# 1_P1_schdoc.net
KiCad netlist of a schematic drawn in Altium Designer
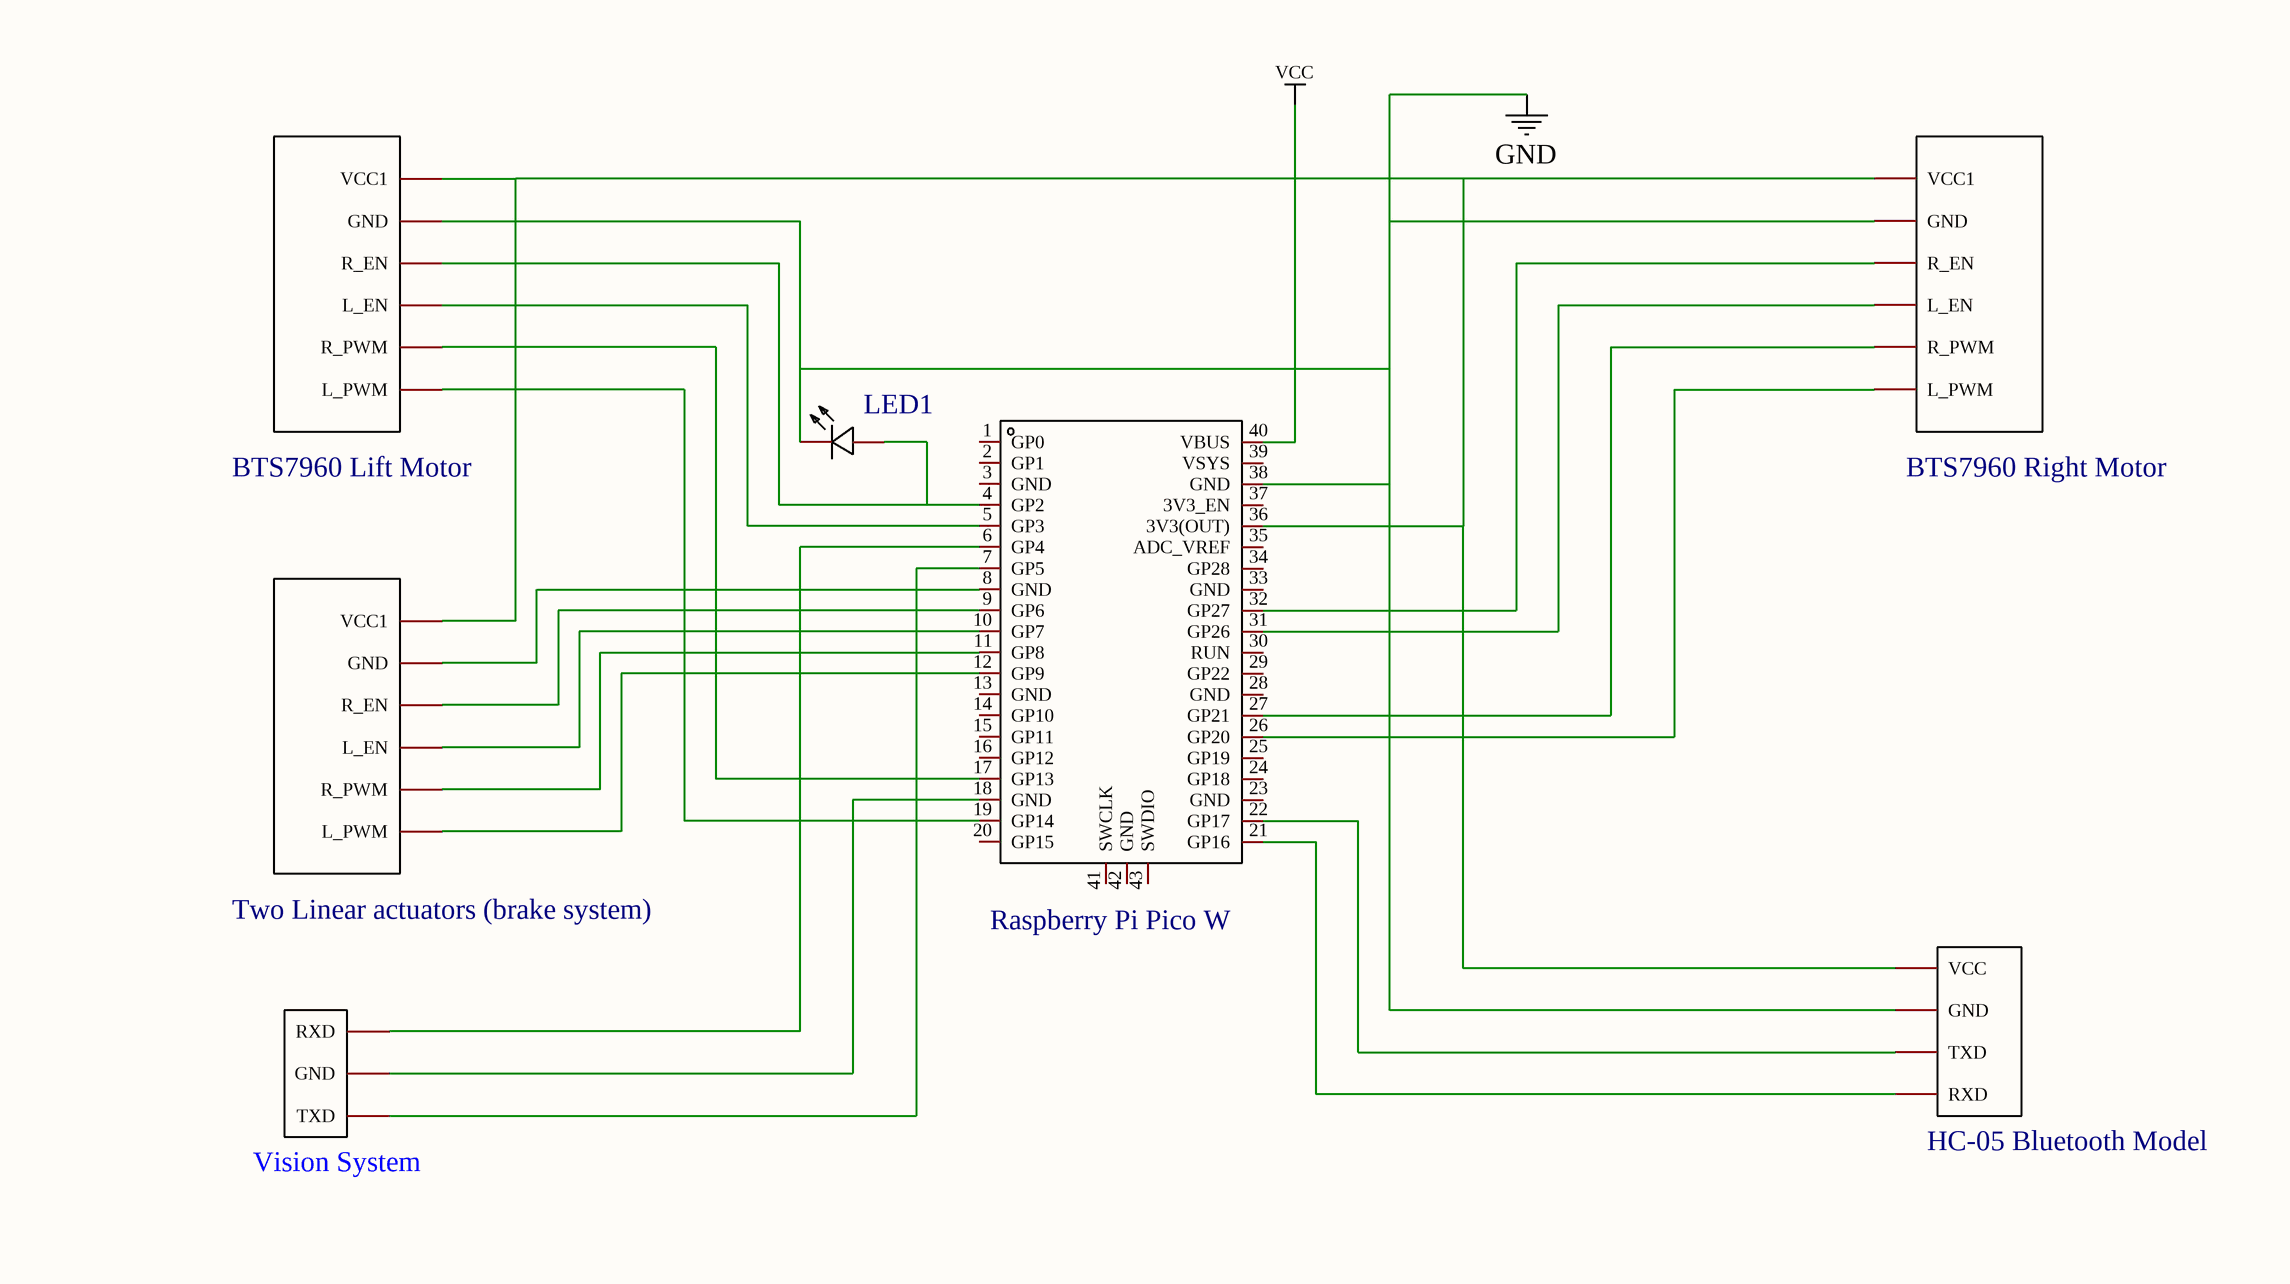
[diagram p0: 1_P1.schdoc.schdoc]

(export (version "E")
  (design (tool "Eeschema 10.0.6"))
  (components
    (comp (ref "LED1")
      (value "NCD0805R1")
      (fields (field (name "MANUFACTURER") "国星光电"))
      (libsource (lib "altium-import") (part "root_0_NCD0805R1_"))
    )
    (comp (ref "U1")
      (value "Raspberry Pi Pico W")
      (fields
        (field (name "NAME") "Raspberry Pi Pico W")
        (field (name "MANUFACTURER") "Raspberry Pi(树莓派)")
        (field (name "MANUFACTURER PART") "PICO")
      )
      (libsource (lib "altium-import") (part "root_0_PICO_"))
    )
    (comp (ref "U2")
      (value "HC-05 Bluetooth Model")
      (fields (field (name "NAME") "HC-05 Bluetooth Model"))
      (libsource (lib "altium-import") (part "root_0_mirrored_HC-05_"))
    )
    (comp (ref "U3")
      (value "BTS7960 Lift Motor")
      (fields (field (name "NAME") "BTS7960 Lift Motor"))
      (libsource (lib "altium-import") (part "root_0_Motor Driver_"))
    )
    (comp (ref "U4")
      (value "BTS7960 Right Motor")
      (fields (field (name "NAME") "BTS7960 Right Motor"))
      (libsource (lib "altium-import") (part "root_0_mirrored_Motor Driver_"))
    )
    (comp (ref "U5")
      (value "Vision System")
      (fields (field (name "DEVICE") "Vision System"))
      (libsource (lib "altium-import") (part "root_0_Vision System_"))
    )
    (comp (ref "U6")
      (value "Two Linear actuators (brake system)")
      (fields (field (name "NAME") "Two Linear actuators (brake system)"))
      (libsource (lib "altium-import") (part "root_0_Motor Driver_"))
    )
  )
  (nets
    (net (code "1") (name "GND") (class "Default")
      (node (ref "LED1") (pin "2") (pinfunction "-_2") (pintype "passive"))
      (node (ref "U1") (pin "38") (pinfunction "GND_38") (pintype "passive"))
      (node (ref "U2") (pin "2") (pinfunction "GND_2") (pintype "passive"))
      (node (ref "U3") (pin "2") (pinfunction "GND_2") (pintype "passive"))
      (node (ref "U4") (pin "2") (pinfunction "GND_2") (pintype "passive"))
    )
    (net (code "2") (name "Net-(LED1-+)") (class "Default")
      (node (ref "LED1") (pin "1") (pinfunction "+_1") (pintype "passive"))
      (node (ref "U1") (pin "4") (pinfunction "GP2_4") (pintype "passive"))
      (node (ref "U3") (pin "3") (pinfunction "R_EN_3") (pintype "passive"))
    )
    (net (code "3") (name "Net-(U1-3V3(OUT))") (class "Default")
      (node (ref "U1") (pin "36") (pinfunction "3V3(OUT)_36") (pintype "passive"))
      (node (ref "U2") (pin "1") (pinfunction "VCC_1") (pintype "passive"))
      (node (ref "U3") (pin "1") (pinfunction "VCC1_1") (pintype "passive"))
      (node (ref "U4") (pin "1") (pinfunction "VCC1_1") (pintype "passive"))
      (node (ref "U6") (pin "1") (pinfunction "VCC1_1") (pintype "passive"))
    )
    (net (code "4") (name "Net-(U1-GP3)") (class "Default")
      (node (ref "U1") (pin "5") (pinfunction "GP3_5") (pintype "passive"))
      (node (ref "U3") (pin "4") (pinfunction "L_EN_4") (pintype "passive"))
    )
    (net (code "5") (name "Net-(U1-GP4)") (class "Default")
      (node (ref "U1") (pin "6") (pinfunction "GP4_6") (pintype "passive"))
      (node (ref "U5") (pin "1") (pinfunction "RXD_1") (pintype "passive"))
    )
    (net (code "6") (name "Net-(U1-GP5)") (class "Default")
      (node (ref "U1") (pin "7") (pinfunction "GP5_7") (pintype "passive"))
      (node (ref "U5") (pin "3") (pinfunction "TXD_3") (pintype "passive"))
    )
    (net (code "7") (name "Net-(U1-GP6)") (class "Default")
      (node (ref "U1") (pin "9") (pinfunction "GP6_9") (pintype "passive"))
      (node (ref "U6") (pin "3") (pinfunction "R_EN_3") (pintype "passive"))
    )
    (net (code "8") (name "Net-(U1-GP7)") (class "Default")
      (node (ref "U1") (pin "10") (pinfunction "GP7_10") (pintype "passive"))
      (node (ref "U6") (pin "4") (pinfunction "L_EN_4") (pintype "passive"))
    )
    (net (code "9") (name "Net-(U1-GP8)") (class "Default")
      (node (ref "U1") (pin "11") (pinfunction "GP8_11") (pintype "passive"))
      (node (ref "U6") (pin "5") (pinfunction "R_PWM_5") (pintype "passive"))
    )
    (net (code "10") (name "Net-(U1-GP9)") (class "Default")
      (node (ref "U1") (pin "12") (pinfunction "GP9_12") (pintype "passive"))
      (node (ref "U6") (pin "6") (pinfunction "L_PWM_6") (pintype "passive"))
    )
    (net (code "11") (name "Net-(U1-GP13)") (class "Default")
      (node (ref "U1") (pin "17") (pinfunction "GP13_17") (pintype "passive"))
      (node (ref "U3") (pin "5") (pinfunction "R_PWM_5") (pintype "passive"))
    )
    (net (code "12") (name "Net-(U1-GP14)") (class "Default")
      (node (ref "U1") (pin "19") (pinfunction "GP14_19") (pintype "passive"))
      (node (ref "U3") (pin "6") (pinfunction "L_PWM_6") (pintype "passive"))
    )
    (net (code "13") (name "Net-(U1-GP16)") (class "Default")
      (node (ref "U1") (pin "21") (pinfunction "GP16_21") (pintype "passive"))
      (node (ref "U2") (pin "4") (pinfunction "RXD_4") (pintype "passive"))
    )
    (net (code "14") (name "Net-(U1-GP17)") (class "Default")
      (node (ref "U1") (pin "22") (pinfunction "GP17_22") (pintype "passive"))
      (node (ref "U2") (pin "3") (pinfunction "TXD_3") (pintype "passive"))
    )
    (net (code "15") (name "Net-(U1-GP20)") (class "Default")
      (node (ref "U1") (pin "26") (pinfunction "GP20_26") (pintype "passive"))
      (node (ref "U4") (pin "6") (pinfunction "L_PWM_6") (pintype "passive"))
    )
    (net (code "16") (name "Net-(U1-GP21)") (class "Default")
      (node (ref "U1") (pin "27") (pinfunction "GP21_27") (pintype "passive"))
      (node (ref "U4") (pin "5") (pinfunction "R_PWM_5") (pintype "passive"))
    )
    (net (code "17") (name "Net-(U1-GP26)") (class "Default")
      (node (ref "U1") (pin "31") (pinfunction "GP26_31") (pintype "passive"))
      (node (ref "U4") (pin "4") (pinfunction "L_EN_4") (pintype "passive"))
    )
    (net (code "18") (name "Net-(U1-GP27)") (class "Default")
      (node (ref "U1") (pin "32") (pinfunction "GP27_32") (pintype "passive"))
      (node (ref "U4") (pin "3") (pinfunction "R_EN_3") (pintype "passive"))
    )
    (net (code "19") (name "Net-(U5-GND)") (class "Default")
      (node (ref "U1") (pin "18") (pinfunction "GND_18") (pintype "passive"))
      (node (ref "U5") (pin "2") (pinfunction "GND_2") (pintype "passive"))
    )
    (net (code "20") (name "Net-(U6-GND)") (class "Default")
      (node (ref "U1") (pin "8") (pinfunction "GND_8") (pintype "passive"))
      (node (ref "U6") (pin "2") (pinfunction "GND_2") (pintype "passive"))
    )
    (net (code "21") (name "VCC") (class "Default")
      (node (ref "U1") (pin "40") (pinfunction "VBUS_40") (pintype "passive"))
    )
    (net (code "22") (name "unconnected-(U1-3V3_EN-Pad37)") (class "Default")
      (node (ref "U1") (pin "37") (pinfunction "3V3_EN_37") (pintype "passive"))
    )
    (net (code "23") (name "unconnected-(U1-ADC_VREF-Pad35)") (class "Default")
      (node (ref "U1") (pin "35") (pinfunction "ADC_VREF_35") (pintype "passive"))
    )
    (net (code "24") (name "unconnected-(U1-GND-Pad3)") (class "Default")
      (node (ref "U1") (pin "3") (pinfunction "GND_3") (pintype "passive"))
    )
    (net (code "25") (name "unconnected-(U1-GND-Pad13)") (class "Default")
      (node (ref "U1") (pin "13") (pinfunction "GND_13") (pintype "passive"))
    )
    (net (code "26") (name "unconnected-(U1-GND-Pad23)") (class "Default")
      (node (ref "U1") (pin "23") (pinfunction "GND_23") (pintype "passive"))
    )
    (net (code "27") (name "unconnected-(U1-GND-Pad28)") (class "Default")
      (node (ref "U1") (pin "28") (pinfunction "GND_28") (pintype "passive"))
    )
    (net (code "28") (name "unconnected-(U1-GND-Pad33)") (class "Default")
      (node (ref "U1") (pin "33") (pinfunction "GND_33") (pintype "passive"))
    )
    (net (code "29") (name "unconnected-(U1-GND-Pad42)") (class "Default")
      (node (ref "U1") (pin "42") (pinfunction "GND_42") (pintype "passive"))
    )
    (net (code "30") (name "unconnected-(U1-GP0-Pad1)") (class "Default")
      (node (ref "U1") (pin "1") (pinfunction "GP0_1") (pintype "passive"))
    )
    (net (code "31") (name "unconnected-(U1-GP1-Pad2)") (class "Default")
      (node (ref "U1") (pin "2") (pinfunction "GP1_2") (pintype "passive"))
    )
    (net (code "32") (name "unconnected-(U1-GP10-Pad14)") (class "Default")
      (node (ref "U1") (pin "14") (pinfunction "GP10_14") (pintype "passive"))
    )
    (net (code "33") (name "unconnected-(U1-GP11-Pad15)") (class "Default")
      (node (ref "U1") (pin "15") (pinfunction "GP11_15") (pintype "passive"))
    )
    (net (code "34") (name "unconnected-(U1-GP12-Pad16)") (class "Default")
      (node (ref "U1") (pin "16") (pinfunction "GP12_16") (pintype "passive"))
    )
    (net (code "35") (name "unconnected-(U1-GP15-Pad20)") (class "Default")
      (node (ref "U1") (pin "20") (pinfunction "GP15_20") (pintype "passive"))
    )
    (net (code "36") (name "unconnected-(U1-GP18-Pad24)") (class "Default")
      (node (ref "U1") (pin "24") (pinfunction "GP18_24") (pintype "passive"))
    )
    (net (code "37") (name "unconnected-(U1-GP19-Pad25)") (class "Default")
      (node (ref "U1") (pin "25") (pinfunction "GP19_25") (pintype "passive"))
    )
    (net (code "38") (name "unconnected-(U1-GP22-Pad29)") (class "Default")
      (node (ref "U1") (pin "29") (pinfunction "GP22_29") (pintype "passive"))
    )
    (net (code "39") (name "unconnected-(U1-GP28-Pad34)") (class "Default")
      (node (ref "U1") (pin "34") (pinfunction "GP28_34") (pintype "passive"))
    )
    (net (code "40") (name "unconnected-(U1-RUN-Pad30)") (class "Default")
      (node (ref "U1") (pin "30") (pinfunction "RUN_30") (pintype "passive"))
    )
    (net (code "41") (name "unconnected-(U1-SWCLK-Pad41)") (class "Default")
      (node (ref "U1") (pin "41") (pinfunction "SWCLK_41") (pintype "passive"))
    )
    (net (code "42") (name "unconnected-(U1-SWDIO-Pad43)") (class "Default")
      (node (ref "U1") (pin "43") (pinfunction "SWDIO_43") (pintype "passive"))
    )
    (net (code "43") (name "unconnected-(U1-VSYS-Pad39)") (class "Default")
      (node (ref "U1") (pin "39") (pinfunction "VSYS_39") (pintype "passive"))
    )
  )
)
